# sensor.net
KiCad netlist of a schematic drawn in EAGLE
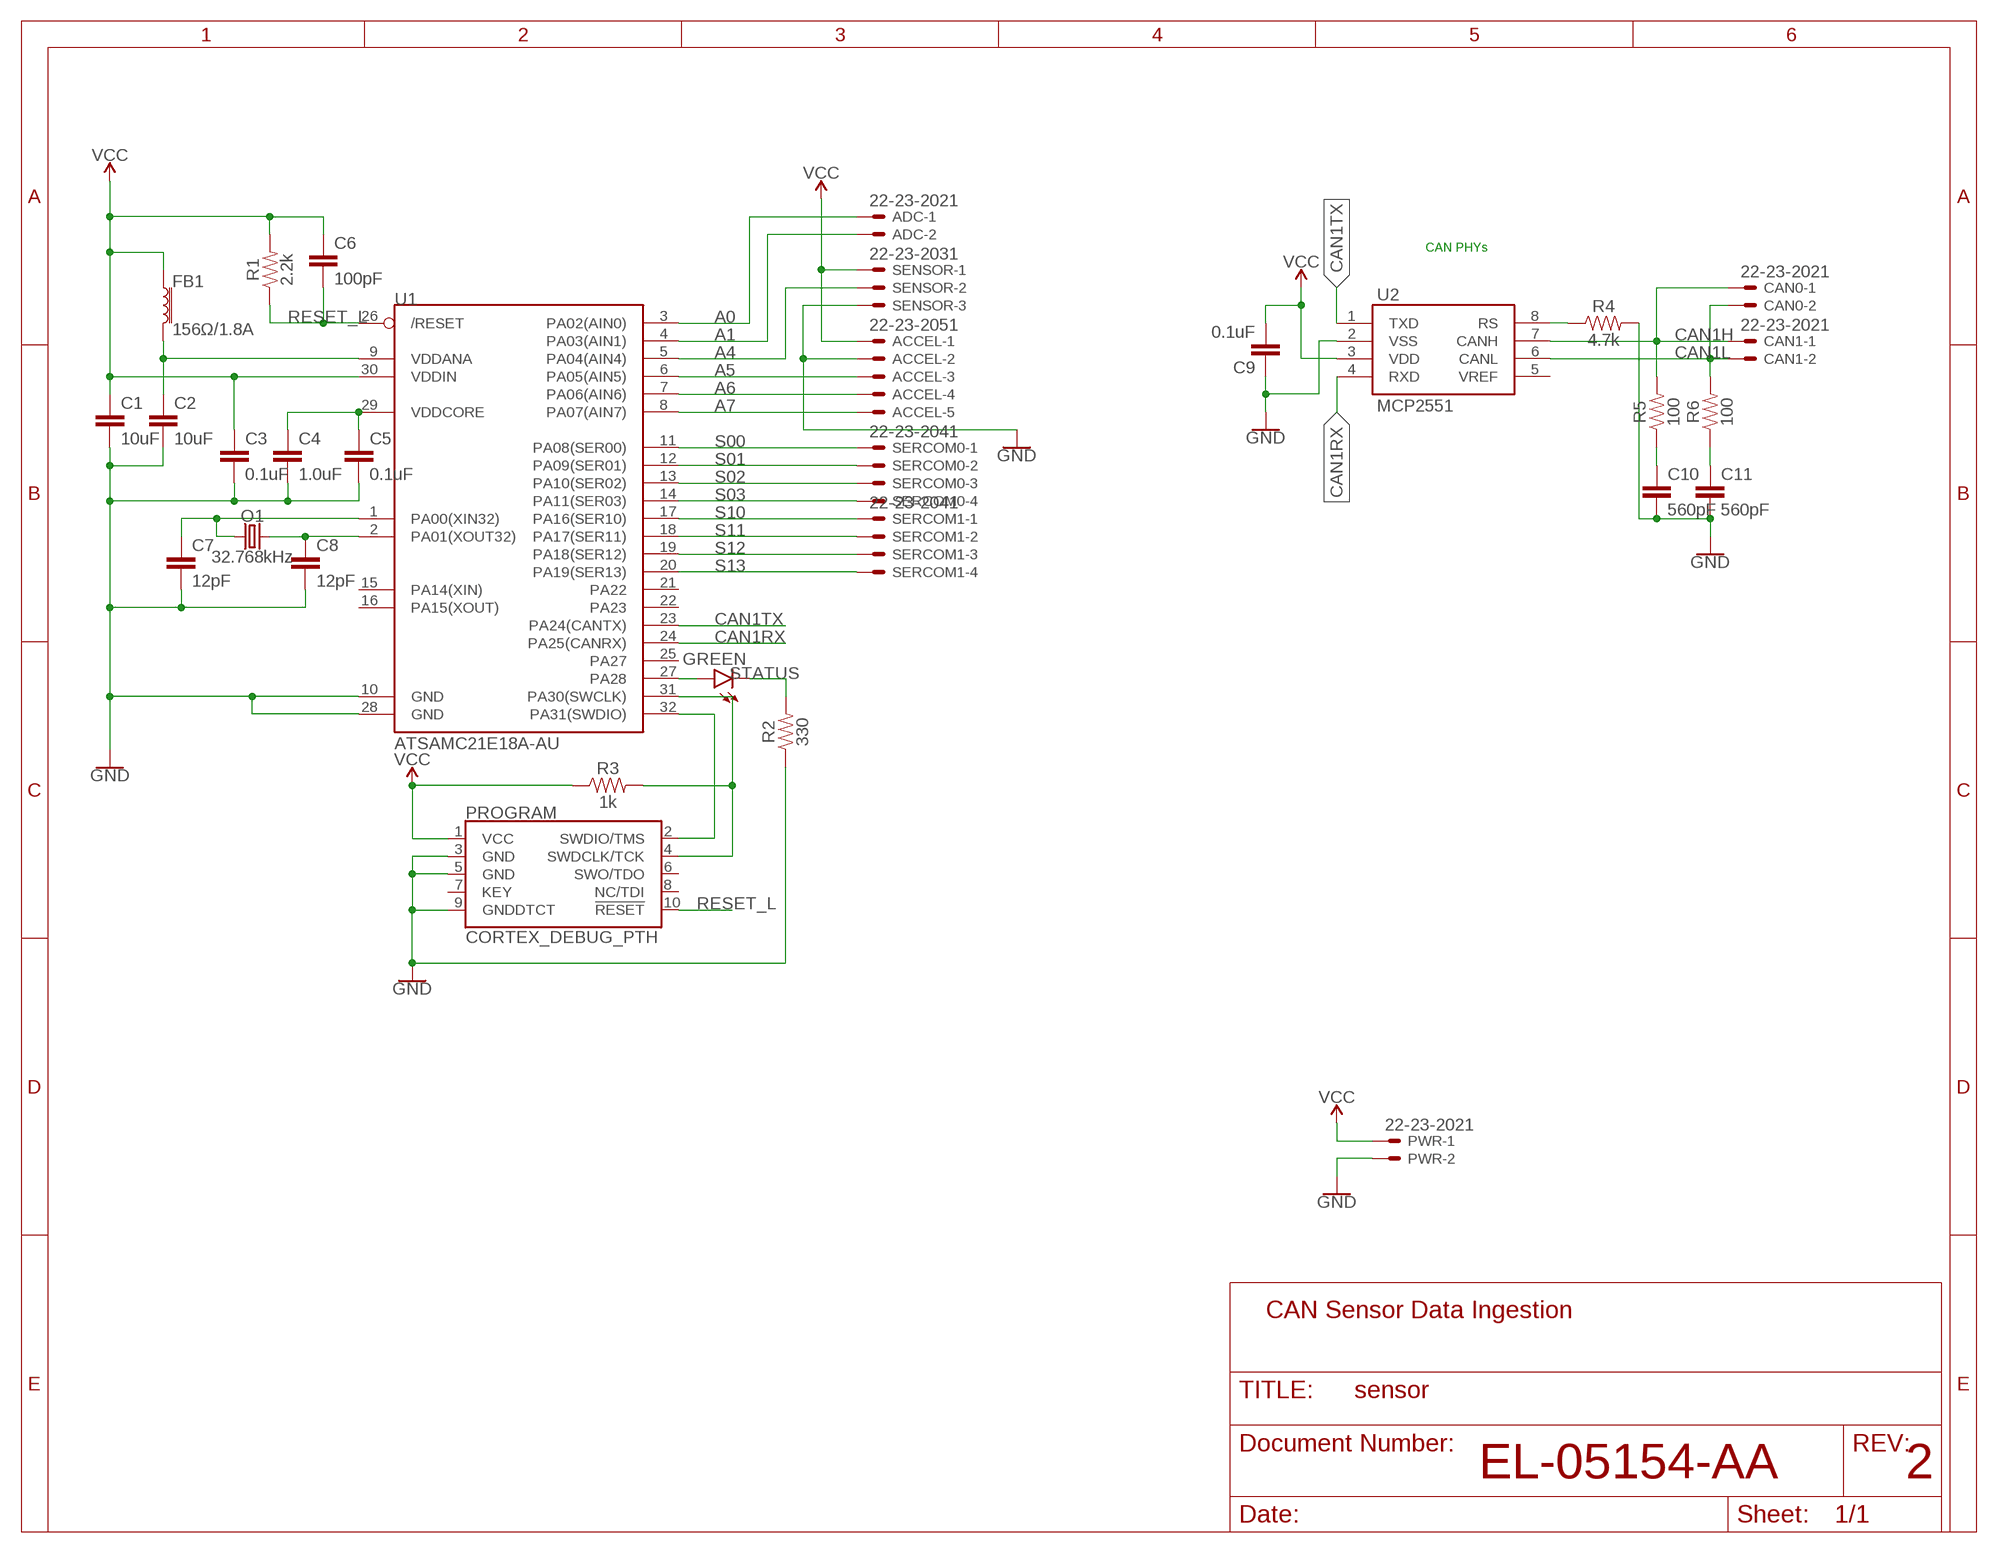
[diagram p0: schematic, sheet 1]

(export (version "E")
  (design (tool "Eeschema 10.0.6"))
  (components
    (comp (ref "ACCEL")
      (value "22-23-2051")
      (footprint "eagle-import:22-23-2051")
      (fields (field (name "MF") "MOLEX"))
      (libsource (lib "eagle-import") (part "22-23-2051"))
    )
    (comp (ref "ADC")
      (value "22-23-2021")
      (footprint "eagle-import:22-23-2021")
      (fields (field (name "MF") "MOLEX"))
      (libsource (lib "eagle-import") (part "22-23-2021"))
    )
    (comp (ref "C1")
      (value "10uF")
      (footprint "eagle-import:0603")
      (libsource (lib "eagle-import") (part "10UF-0603-6.3V-20%"))
    )
    (comp (ref "C2")
      (value "10uF")
      (footprint "eagle-import:0603")
      (libsource (lib "eagle-import") (part "10UF-0603-6.3V-20%"))
    )
    (comp (ref "C3")
      (value "0.1uF")
      (footprint "eagle-import:0603")
      (libsource (lib "eagle-import") (part "0.1UF-0603-25V-(+80/-20%)"))
    )
    (comp (ref "C4")
      (value "1.0uF")
      (footprint "eagle-import:0603")
      (libsource (lib "eagle-import") (part "1.0UF-0603-16V-10%"))
    )
    (comp (ref "C5")
      (value "0.1uF")
      (footprint "eagle-import:0603")
      (libsource (lib "eagle-import") (part "0.1UF-0603-25V-(+80/-20%)"))
    )
    (comp (ref "C6")
      (value "100pF")
      (footprint "eagle-import:0603")
      (libsource (lib "eagle-import") (part "100PF-0603-50V-5%"))
    )
    (comp (ref "C7")
      (value "12pF")
      (footprint "eagle-import:0603")
      (libsource (lib "eagle-import") (part "12PF-0603-50V-5%"))
    )
    (comp (ref "C8")
      (value "12pF")
      (footprint "eagle-import:0603")
      (libsource (lib "eagle-import") (part "12PF-0603-50V-5%"))
    )
    (comp (ref "C9")
      (value "0.1uF")
      (footprint "eagle-import:0603")
      (libsource (lib "eagle-import") (part "0.1UF-0603-25V-(+80/-20%)"))
    )
    (comp (ref "C10")
      (value "560pF")
      (footprint "eagle-import:0603")
      (libsource (lib "eagle-import") (part "560PF-0603-50V-5%"))
    )
    (comp (ref "C11")
      (value "560pF")
      (footprint "eagle-import:0603")
      (libsource (lib "eagle-import") (part "560PF-0603-50V-5%"))
    )
    (comp (ref "CAN0")
      (value "22-23-2021")
      (footprint "eagle-import:22-23-2021")
      (fields (field (name "MF") "MOLEX"))
      (libsource (lib "eagle-import") (part "22-23-2021"))
    )
    (comp (ref "CAN1")
      (value "22-23-2021")
      (footprint "eagle-import:22-23-2021")
      (fields (field (name "MF") "MOLEX"))
      (libsource (lib "eagle-import") (part "22-23-2021"))
    )
    (comp (ref "FB1")
      (value "156Ω/1.8A")
      (footprint "eagle-import:0603")
      (libsource (lib "eagle-import") (part "FERRITE_BEAD-0603"))
    )
    (comp (ref "O1")
      (value "32.768kHz")
      (footprint "eagle-import:CRYSTAL-PTH-2X6-CYL")
      (libsource (lib "eagle-import") (part "CRYSTAL-32.768KHZPTH-2X6"))
    )
    (comp (ref "PROGRAM")
      (value "CORTEX_DEBUG_PTH")
      (footprint "eagle-import:2X5-PTH-1.27MM")
      (libsource (lib "eagle-import") (part "CORTEX_DEBUG_PTH"))
    )
    (comp (ref "PWR")
      (value "22-23-2021")
      (footprint "eagle-import:22-23-2021")
      (fields (field (name "MF") "MOLEX"))
      (libsource (lib "eagle-import") (part "22-23-2021"))
    )
    (comp (ref "R1")
      (value "2.2k")
      (footprint "eagle-import:0603")
      (libsource (lib "eagle-import") (part "2.2KOHM-0603-1/10W-1%"))
    )
    (comp (ref "R2")
      (value "330")
      (footprint "eagle-import:0603")
      (libsource (lib "eagle-import") (part "330OHM-0603-1/10W-1%"))
    )
    (comp (ref "R3")
      (value "1k")
      (footprint "eagle-import:0603")
      (libsource (lib "eagle-import") (part "1KOHM-0603-1/10W-1%"))
    )
    (comp (ref "R4")
      (value "4.7k")
      (footprint "eagle-import:0603")
      (libsource (lib "eagle-import") (part "4.7KOHM-0603-1/10W-1%"))
    )
    (comp (ref "R5")
      (value "100")
      (footprint "eagle-import:0603")
      (libsource (lib "eagle-import") (part "100OHM-0603-1/4W-5%"))
    )
    (comp (ref "R6")
      (value "100")
      (footprint "eagle-import:0603")
      (libsource (lib "eagle-import") (part "100OHM-0603-1/4W-5%"))
    )
    (comp (ref "SENSOR")
      (value "22-23-2031")
      (footprint "eagle-import:22-23-2031")
      (fields (field (name "MF") "MOLEX"))
      (libsource (lib "eagle-import") (part "22-23-2031"))
    )
    (comp (ref "SERCOM0")
      (value "22-23-2041")
      (footprint "eagle-import:22-23-2041")
      (fields (field (name "MF") "MOLEX"))
      (libsource (lib "eagle-import") (part "22-23-2041"))
    )
    (comp (ref "SERCOM1")
      (value "22-23-2041")
      (footprint "eagle-import:22-23-2041")
      (fields (field (name "MF") "MOLEX"))
      (libsource (lib "eagle-import") (part "22-23-2041"))
    )
    (comp (ref "STATUS")
      (value "GREEN")
      (footprint "eagle-import:LED_3MM")
      (libsource (lib "eagle-import") (part "LED3MM"))
    )
    (comp (ref "U1")
      (value "ATSAMC21E18A-AU")
      (footprint "eagle-import:TQFP32-08")
      (libsource (lib "eagle-import") (part "ATSAMC21E18A-AU"))
    )
    (comp (ref "U2")
      (value "MCP2551")
      (footprint "eagle-import:SO08")
      (libsource (lib "eagle-import") (part "MCP2551"))
    )
  )
  (nets
    (net (code "1") (name "/A0") (class "Default")
      (node (ref "ADC") (pin "1") (pinfunction "S_1") (pintype "passive"))
      (node (ref "U1") (pin "3") (pinfunction "PA02(AIN0)_3") (pintype "bidirectional"))
    )
    (net (code "2") (name "/A1") (class "Default")
      (node (ref "ADC") (pin "2") (pinfunction "S_2") (pintype "passive"))
      (node (ref "U1") (pin "4") (pinfunction "PA03(AIN1)_4") (pintype "bidirectional"))
    )
    (net (code "3") (name "/A4") (class "Default")
      (node (ref "SENSOR") (pin "2") (pinfunction "S_2") (pintype "passive"))
      (node (ref "U1") (pin "5") (pinfunction "PA04(AIN4)_5") (pintype "bidirectional"))
    )
    (net (code "4") (name "/A5") (class "Default")
      (node (ref "ACCEL") (pin "3") (pinfunction "S_3") (pintype "passive"))
      (node (ref "U1") (pin "6") (pinfunction "PA05(AIN5)_6") (pintype "bidirectional"))
    )
    (net (code "5") (name "/A6") (class "Default")
      (node (ref "ACCEL") (pin "4") (pinfunction "S_4") (pintype "passive"))
      (node (ref "U1") (pin "7") (pinfunction "PA06(AIN6)_7") (pintype "bidirectional"))
    )
    (net (code "6") (name "/A7") (class "Default")
      (node (ref "ACCEL") (pin "5") (pinfunction "S_5") (pintype "passive"))
      (node (ref "U1") (pin "8") (pinfunction "PA07(AIN7)_8") (pintype "bidirectional"))
    )
    (net (code "7") (name "/CAN1H") (class "Default")
      (node (ref "CAN0") (pin "1") (pinfunction "S_1") (pintype "passive"))
      (node (ref "CAN1") (pin "1") (pinfunction "S_1") (pintype "passive"))
      (node (ref "R5") (pin "2") (pinfunction "2_2") (pintype "passive"))
      (node (ref "U2") (pin "7") (pinfunction "CANH_7") (pintype "bidirectional"))
    )
    (net (code "8") (name "/CAN1L") (class "Default")
      (node (ref "CAN0") (pin "2") (pinfunction "S_2") (pintype "passive"))
      (node (ref "CAN1") (pin "2") (pinfunction "S_2") (pintype "passive"))
      (node (ref "R6") (pin "2") (pinfunction "2_2") (pintype "passive"))
      (node (ref "U2") (pin "6") (pinfunction "CANL_6") (pintype "bidirectional"))
    )
    (net (code "9") (name "/RESET_L") (class "Default")
      (node (ref "C6") (pin "2") (pinfunction "2_2") (pintype "passive"))
      (node (ref "PROGRAM") (pin "10") (pinfunction "~{RESET}_10") (pintype "bidirectional"))
      (node (ref "R1") (pin "1") (pinfunction "1_1") (pintype "passive"))
      (node (ref "U1") (pin "26") (pinfunction "/RESET_26") (pintype "input"))
    )
    (net (code "10") (name "/S00") (class "Default")
      (node (ref "SERCOM0") (pin "1") (pinfunction "S_1") (pintype "passive"))
      (node (ref "U1") (pin "11") (pinfunction "PA08(SER00)_11") (pintype "bidirectional"))
    )
    (net (code "11") (name "/S01") (class "Default")
      (node (ref "SERCOM0") (pin "2") (pinfunction "S_2") (pintype "passive"))
      (node (ref "U1") (pin "12") (pinfunction "PA09(SER01)_12") (pintype "bidirectional"))
    )
    (net (code "12") (name "/S02") (class "Default")
      (node (ref "SERCOM0") (pin "3") (pinfunction "S_3") (pintype "passive"))
      (node (ref "U1") (pin "13") (pinfunction "PA10(SER02)_13") (pintype "bidirectional"))
    )
    (net (code "13") (name "/S03") (class "Default")
      (node (ref "SERCOM0") (pin "4") (pinfunction "S_4") (pintype "passive"))
      (node (ref "U1") (pin "14") (pinfunction "PA11(SER03)_14") (pintype "bidirectional"))
    )
    (net (code "14") (name "/S10") (class "Default")
      (node (ref "SERCOM1") (pin "1") (pinfunction "S_1") (pintype "passive"))
      (node (ref "U1") (pin "17") (pinfunction "PA16(SER10)_17") (pintype "bidirectional"))
    )
    (net (code "15") (name "/S11") (class "Default")
      (node (ref "SERCOM1") (pin "2") (pinfunction "S_2") (pintype "passive"))
      (node (ref "U1") (pin "18") (pinfunction "PA17(SER11)_18") (pintype "bidirectional"))
    )
    (net (code "16") (name "/S12") (class "Default")
      (node (ref "SERCOM1") (pin "3") (pinfunction "S_3") (pintype "passive"))
      (node (ref "U1") (pin "19") (pinfunction "PA18(SER12)_19") (pintype "bidirectional"))
    )
    (net (code "17") (name "/S13") (class "Default")
      (node (ref "SERCOM1") (pin "4") (pinfunction "S_4") (pintype "passive"))
      (node (ref "U1") (pin "20") (pinfunction "PA19(SER13)_20") (pintype "bidirectional"))
    )
    (net (code "18") (name "CAN1RX") (class "Default")
      (node (ref "U1") (pin "24") (pinfunction "PA25(CANRX)_24") (pintype "bidirectional"))
      (node (ref "U2") (pin "4") (pinfunction "RXD_4") (pintype "bidirectional"))
    )
    (net (code "19") (name "CAN1TX") (class "Default")
      (node (ref "U1") (pin "23") (pinfunction "PA24(CANTX)_23") (pintype "bidirectional"))
      (node (ref "U2") (pin "1") (pinfunction "TXD_1") (pintype "bidirectional"))
    )
    (net (code "20") (name "GND") (class "Default")
      (node (ref "ACCEL") (pin "2") (pinfunction "S_2") (pintype "passive"))
      (node (ref "C1") (pin "2") (pinfunction "2_2") (pintype "passive"))
      (node (ref "C10") (pin "2") (pinfunction "2_2") (pintype "passive"))
      (node (ref "C11") (pin "2") (pinfunction "2_2") (pintype "passive"))
      (node (ref "C2") (pin "2") (pinfunction "2_2") (pintype "passive"))
      (node (ref "C3") (pin "2") (pinfunction "2_2") (pintype "passive"))
      (node (ref "C4") (pin "2") (pinfunction "2_2") (pintype "passive"))
      (node (ref "C5") (pin "2") (pinfunction "2_2") (pintype "passive"))
      (node (ref "C7") (pin "2") (pinfunction "2_2") (pintype "passive"))
      (node (ref "C8") (pin "2") (pinfunction "2_2") (pintype "passive"))
      (node (ref "C9") (pin "1") (pinfunction "1_1") (pintype "passive"))
      (node (ref "PROGRAM") (pin "3") (pinfunction "GND_3") (pintype "bidirectional"))
      (node (ref "PROGRAM") (pin "5") (pinfunction "GND_5") (pintype "bidirectional"))
      (node (ref "PROGRAM") (pin "9") (pinfunction "GNDDTCT_9") (pintype "bidirectional"))
      (node (ref "PWR") (pin "2") (pinfunction "S_2") (pintype "passive"))
      (node (ref "R2") (pin "1") (pinfunction "1_1") (pintype "passive"))
      (node (ref "R4") (pin "2") (pinfunction "2_2") (pintype "passive"))
      (node (ref "SENSOR") (pin "3") (pinfunction "S_3") (pintype "passive"))
      (node (ref "U1") (pin "10") (pinfunction "GND_10") (pintype "power_in"))
      (node (ref "U1") (pin "28") (pinfunction "GND_28") (pintype "power_in"))
      (node (ref "U2") (pin "2") (pinfunction "VSS_2") (pintype "bidirectional"))
    )
    (net (code "21") (name "Net-(C10-Pad1)") (class "Default")
      (node (ref "C10") (pin "1") (pinfunction "1_1") (pintype "passive"))
      (node (ref "R5") (pin "1") (pinfunction "1_1") (pintype "passive"))
    )
    (net (code "22") (name "Net-(C11-Pad1)") (class "Default")
      (node (ref "C11") (pin "1") (pinfunction "1_1") (pintype "passive"))
      (node (ref "R6") (pin "1") (pinfunction "1_1") (pintype "passive"))
    )
    (net (code "23") (name "Net-(PROGRAM-SWDCLK{slash}TCK)") (class "Default")
      (node (ref "PROGRAM") (pin "4") (pinfunction "SWDCLK/TCK_4") (pintype "bidirectional"))
      (node (ref "R3") (pin "2") (pinfunction "2_2") (pintype "passive"))
      (node (ref "U1") (pin "31") (pinfunction "PA30(SWCLK)_31") (pintype "bidirectional"))
    )
    (net (code "24") (name "Net-(PROGRAM-SWDIO{slash}TMS)") (class "Default")
      (node (ref "PROGRAM") (pin "2") (pinfunction "SWDIO/TMS_2") (pintype "bidirectional"))
      (node (ref "U1") (pin "32") (pinfunction "PA31(SWDIO)_32") (pintype "bidirectional"))
    )
    (net (code "25") (name "Net-(STATUS-C)") (class "Default")
      (node (ref "R2") (pin "2") (pinfunction "2_2") (pintype "passive"))
      (node (ref "STATUS") (pin "K") (pinfunction "C_K") (pintype "passive"))
    )
    (net (code "26") (name "Net-(U1-PA00(XIN32))") (class "Default")
      (node (ref "C7") (pin "1") (pinfunction "1_1") (pintype "passive"))
      (node (ref "O1") (pin "1") (pinfunction "1_1") (pintype "passive"))
      (node (ref "U1") (pin "1") (pinfunction "PA00(XIN32)_1") (pintype "bidirectional"))
    )
    (net (code "27") (name "Net-(U1-PA01(XOUT32))") (class "Default")
      (node (ref "C8") (pin "1") (pinfunction "1_1") (pintype "passive"))
      (node (ref "O1") (pin "2") (pinfunction "2_2") (pintype "passive"))
      (node (ref "U1") (pin "2") (pinfunction "PA01(XOUT32)_2") (pintype "bidirectional"))
    )
    (net (code "28") (name "Net-(U1-PA28)") (class "Default")
      (node (ref "STATUS") (pin "A") (pinfunction "A_A") (pintype "passive"))
      (node (ref "U1") (pin "27") (pinfunction "PA28_27") (pintype "bidirectional"))
    )
    (net (code "29") (name "Net-(U1-VDDANA)") (class "Default")
      (node (ref "C2") (pin "1") (pinfunction "1_1") (pintype "passive"))
      (node (ref "FB1") (pin "2") (pinfunction "2_2") (pintype "passive"))
      (node (ref "U1") (pin "9") (pinfunction "VDDANA_9") (pintype "power_in"))
    )
    (net (code "30") (name "Net-(U1-VDDCORE)") (class "Default")
      (node (ref "C4") (pin "1") (pinfunction "1_1") (pintype "passive"))
      (node (ref "C5") (pin "1") (pinfunction "1_1") (pintype "passive"))
      (node (ref "U1") (pin "29") (pinfunction "VDDCORE_29") (pintype "output"))
    )
    (net (code "31") (name "Net-(U2-RS)") (class "Default")
      (node (ref "R4") (pin "1") (pinfunction "1_1") (pintype "passive"))
      (node (ref "U2") (pin "8") (pinfunction "RS_8") (pintype "bidirectional"))
    )
    (net (code "32") (name "VCC") (class "Default")
      (node (ref "ACCEL") (pin "1") (pinfunction "S_1") (pintype "passive"))
      (node (ref "C1") (pin "1") (pinfunction "1_1") (pintype "passive"))
      (node (ref "C3") (pin "1") (pinfunction "1_1") (pintype "passive"))
      (node (ref "C6") (pin "1") (pinfunction "1_1") (pintype "passive"))
      (node (ref "C9") (pin "2") (pinfunction "2_2") (pintype "passive"))
      (node (ref "FB1") (pin "1") (pinfunction "1_1") (pintype "passive"))
      (node (ref "PROGRAM") (pin "1") (pinfunction "VCC_1") (pintype "bidirectional"))
      (node (ref "PWR") (pin "1") (pinfunction "S_1") (pintype "passive"))
      (node (ref "R1") (pin "2") (pinfunction "2_2") (pintype "passive"))
      (node (ref "R3") (pin "1") (pinfunction "1_1") (pintype "passive"))
      (node (ref "SENSOR") (pin "1") (pinfunction "S_1") (pintype "passive"))
      (node (ref "U1") (pin "30") (pinfunction "VDDIN_30") (pintype "power_in"))
      (node (ref "U2") (pin "3") (pinfunction "VDD_3") (pintype "bidirectional"))
    )
    (net (code "33") (name "unconnected-(PROGRAM-KEY-Pad7)") (class "Default")
      (node (ref "PROGRAM") (pin "7") (pinfunction "KEY_7") (pintype "bidirectional"))
    )
    (net (code "34") (name "unconnected-(PROGRAM-NC{slash}TDI-Pad8)") (class "Default")
      (node (ref "PROGRAM") (pin "8") (pinfunction "NC/TDI_8") (pintype "bidirectional"))
    )
    (net (code "35") (name "unconnected-(PROGRAM-SWO{slash}TDO-Pad6)") (class "Default")
      (node (ref "PROGRAM") (pin "6") (pinfunction "SWO/TDO_6") (pintype "bidirectional"))
    )
    (net (code "36") (name "unconnected-(U1-PA14(XIN)-Pad15)") (class "Default")
      (node (ref "U1") (pin "15") (pinfunction "PA14(XIN)_15") (pintype "bidirectional"))
    )
    (net (code "37") (name "unconnected-(U1-PA15(XOUT)-Pad16)") (class "Default")
      (node (ref "U1") (pin "16") (pinfunction "PA15(XOUT)_16") (pintype "bidirectional"))
    )
    (net (code "38") (name "unconnected-(U1-PA22-Pad21)") (class "Default")
      (node (ref "U1") (pin "21") (pinfunction "PA22_21") (pintype "bidirectional"))
    )
    (net (code "39") (name "unconnected-(U1-PA23-Pad22)") (class "Default")
      (node (ref "U1") (pin "22") (pinfunction "PA23_22") (pintype "bidirectional"))
    )
    (net (code "40") (name "unconnected-(U1-PA27-Pad25)") (class "Default")
      (node (ref "U1") (pin "25") (pinfunction "PA27_25") (pintype "bidirectional"))
    )
    (net (code "41") (name "unconnected-(U2-VREF-Pad5)") (class "Default")
      (node (ref "U2") (pin "5") (pinfunction "VREF_5") (pintype "bidirectional"))
    )
  )
)
